# MCU.net
KiCad netlist of a schematic drawn in Altium Designer
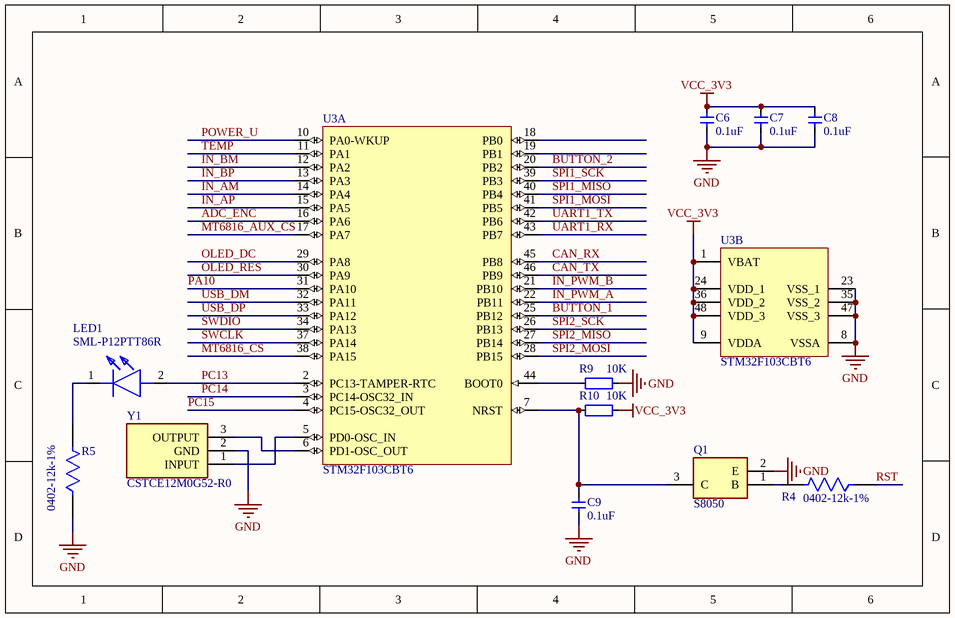
[diagram p0: MCU.SchDoc]

(export (version "E")
  (design (tool "Eeschema 10.0.6"))
  (components
    (comp (ref "C6")
      (value "0.1uF")
      (footprint "CAP_0402")
      (description "Capacitor")
      (libsource (lib "MyPcbLib") (part "电容-0402"))
    )
    (comp (ref "C7")
      (value "0.1uF")
      (footprint "CAP_0402")
      (description "Capacitor")
      (libsource (lib "MyPcbLib") (part "电容-0402"))
    )
    (comp (ref "C8")
      (value "0.1uF")
      (footprint "CAP_0402")
      (description "Capacitor")
      (libsource (lib "MyPcbLib") (part "电容-0402"))
    )
    (comp (ref "C9")
      (value "0.1uF")
      (footprint "CAP_0402")
      (description "Capacitor")
      (libsource (lib "MyPcbLib") (part "电容-0402"))
    )
    (comp (ref "LED1")
      (value "SML-P12PTT86R")
      (footprint "SamacSys:LEDC1006X25N")
      (description "LED")
      (fields (field (name "MOUSER PART NUMBER") "755-SML-P12PTT86R"))
      (libsource (lib "*") (part "SML-P12PTT86R"))
    )
    (comp (ref "Q1")
      (value "S8050")
      (footprint "SamacSys:SOT95P240X115-3N")
      (description "Transistor")
      (libsource (lib "SamacSys") (part "S8050"))
    )
    (comp (ref "R4")
      (value "0402-12k-1%")
      (footprint "FP-CRCW0402-e3-IPC_C")
      (description "RES Thick Film, 0Ω, 0.063W, 0402")
      (fields (field (name "TOLERANCE") "5%"))
      (libsource (lib "Altium Content Vault") (part "1029c3af85768c4190bb7ad29bc67b5"))
    )
    (comp (ref "R5")
      (value "0402-12k-1%")
      (footprint "FP-CRCW0402-e3-IPC_C")
      (description "RES Thick Film, 0Ω, 0.063W, 0402")
      (fields (field (name "TOLERANCE") "5%"))
      (libsource (lib "Altium Content Vault") (part "1029c3af85768c4190bb7ad29bc67b5"))
    )
    (comp (ref "R9")
      (value "10K")
      (footprint "RES_0402")
      (description "Resistor")
      (libsource (lib "MyPcbLib") (part "电阻-0402"))
    )
    (comp (ref "R10")
      (value "10K")
      (footprint "RES_0402")
      (description "Resistor")
      (libsource (lib "MyPcbLib") (part "电阻-0402"))
    )
    (comp (ref "U3")
      (value "STM32F103CBT6")
      (footprint "LQFP-48")
      (libsource (lib "STMicroelectronics STM32 F1") (part "STM32F103CBT6"))
    )
    (comp (ref "Y1")
      (value "CSTCE12M0G52-R0")
      (footprint "SamacSys:CSTCE12M0G52R0")
      (description "Crystal or Oscillator")
      (fields (field (name "MOUSER PART NUMBER") "81-CSTCE12M0G52-R0"))
      (libsource (lib "*") (part "CSTCE12M0G52-R0"))
    )
  )
  (nets
    (net (code "1") (name "/ADC_ENC") (class "Default")
      (node (ref "U3") (pin "16") (pinfunction "PA6_16") (pintype "bidirectional"))
    )
    (net (code "2") (name "/BUTTON_1") (class "Default")
      (node (ref "U3") (pin "25") (pinfunction "PB12_25") (pintype "bidirectional"))
    )
    (net (code "3") (name "/BUTTON_2") (class "Default")
      (node (ref "U3") (pin "20") (pinfunction "PB2_20") (pintype "bidirectional"))
    )
    (net (code "4") (name "/CAN_RX") (class "Default")
      (node (ref "U3") (pin "45") (pinfunction "PB8_45") (pintype "bidirectional"))
    )
    (net (code "5") (name "/CAN_TX") (class "Default")
      (node (ref "U3") (pin "46") (pinfunction "PB9_46") (pintype "bidirectional"))
    )
    (net (code "6") (name "/IN_AM") (class "Default")
      (node (ref "U3") (pin "14") (pinfunction "PA4_14") (pintype "bidirectional"))
    )
    (net (code "7") (name "/IN_AP") (class "Default")
      (node (ref "U3") (pin "15") (pinfunction "PA5_15") (pintype "bidirectional"))
    )
    (net (code "8") (name "/IN_BM") (class "Default")
      (node (ref "U3") (pin "12") (pinfunction "PA2_12") (pintype "bidirectional"))
    )
    (net (code "9") (name "/IN_BP") (class "Default")
      (node (ref "U3") (pin "13") (pinfunction "PA3_13") (pintype "bidirectional"))
    )
    (net (code "10") (name "/IN_PWM_A") (class "Default")
      (node (ref "U3") (pin "22") (pinfunction "PB11_22") (pintype "bidirectional"))
    )
    (net (code "11") (name "/IN_PWM_B") (class "Default")
      (node (ref "U3") (pin "21") (pinfunction "PB10_21") (pintype "bidirectional"))
    )
    (net (code "12") (name "/MT6816_AUX_CS") (class "Default")
      (node (ref "U3") (pin "17") (pinfunction "PA7_17") (pintype "bidirectional"))
    )
    (net (code "13") (name "/MT6816_CS") (class "Default")
      (node (ref "U3") (pin "38") (pinfunction "PA15_38") (pintype "bidirectional"))
    )
    (net (code "14") (name "/OLED_DC") (class "Default")
      (node (ref "U3") (pin "29") (pinfunction "PA8_29") (pintype "bidirectional"))
    )
    (net (code "15") (name "/OLED_RES") (class "Default")
      (node (ref "U3") (pin "30") (pinfunction "PA9_30") (pintype "bidirectional"))
    )
    (net (code "16") (name "/PA10") (class "Default")
      (node (ref "U3") (pin "31") (pinfunction "PA10_31") (pintype "bidirectional"))
    )
    (net (code "17") (name "/PC13") (class "Default")
      (node (ref "LED1") (pin "2") (pinfunction "A_2") (pintype "passive"))
      (node (ref "U3") (pin "2") (pinfunction "PC13-TAMPER-RTC_2") (pintype "bidirectional"))
    )
    (net (code "18") (name "/PC14") (class "Default")
      (node (ref "U3") (pin "3") (pinfunction "PC14-OSC32_IN_3") (pintype "bidirectional"))
    )
    (net (code "19") (name "/PC15") (class "Default")
      (node (ref "U3") (pin "4") (pinfunction "PC15-OSC32_OUT_4") (pintype "bidirectional"))
    )
    (net (code "20") (name "/POWER_U") (class "Default")
      (node (ref "U3") (pin "10") (pinfunction "PA0-WKUP_10") (pintype "bidirectional"))
    )
    (net (code "21") (name "/RST") (class "Default")
      (node (ref "R4") (pin "1") (pinfunction "1_1") (pintype "passive"))
    )
    (net (code "22") (name "/SPI1_MISO") (class "Default")
      (node (ref "U3") (pin "40") (pinfunction "PB4_40") (pintype "bidirectional"))
    )
    (net (code "23") (name "/SPI1_MOSI") (class "Default")
      (node (ref "U3") (pin "41") (pinfunction "PB5_41") (pintype "bidirectional"))
    )
    (net (code "24") (name "/SPI1_SCK") (class "Default")
      (node (ref "U3") (pin "39") (pinfunction "PB3_39") (pintype "bidirectional"))
    )
    (net (code "25") (name "/SPI2_MISO") (class "Default")
      (node (ref "U3") (pin "27") (pinfunction "PB14_27") (pintype "bidirectional"))
    )
    (net (code "26") (name "/SPI2_MOSI") (class "Default")
      (node (ref "U3") (pin "28") (pinfunction "PB15_28") (pintype "bidirectional"))
    )
    (net (code "27") (name "/SPI2_SCK") (class "Default")
      (node (ref "U3") (pin "26") (pinfunction "PB13_26") (pintype "bidirectional"))
    )
    (net (code "28") (name "/SWCLK") (class "Default")
      (node (ref "U3") (pin "37") (pinfunction "PA14_37") (pintype "bidirectional"))
    )
    (net (code "29") (name "/SWDIO") (class "Default")
      (node (ref "U3") (pin "34") (pinfunction "PA13_34") (pintype "bidirectional"))
    )
    (net (code "30") (name "/TEMP") (class "Default")
      (node (ref "U3") (pin "11") (pinfunction "PA1_11") (pintype "bidirectional"))
    )
    (net (code "31") (name "/UART1_RX") (class "Default")
      (node (ref "U3") (pin "43") (pinfunction "PB7_43") (pintype "bidirectional"))
    )
    (net (code "32") (name "/UART1_TX") (class "Default")
      (node (ref "U3") (pin "42") (pinfunction "PB6_42") (pintype "bidirectional"))
    )
    (net (code "33") (name "/USB_DM") (class "Default")
      (node (ref "U3") (pin "32") (pinfunction "PA11_32") (pintype "bidirectional"))
    )
    (net (code "34") (name "/USB_DP") (class "Default")
      (node (ref "U3") (pin "33") (pinfunction "PA12_33") (pintype "bidirectional"))
    )
    (net (code "35") (name "GND") (class "Default")
      (node (ref "C6") (pin "1") (pinfunction "1_1") (pintype "passive"))
      (node (ref "C7") (pin "1") (pinfunction "1_1") (pintype "passive"))
      (node (ref "C8") (pin "1") (pinfunction "1_1") (pintype "passive"))
      (node (ref "C9") (pin "1") (pinfunction "1_1") (pintype "passive"))
      (node (ref "Q1") (pin "2") (pinfunction "E_2") (pintype "passive"))
      (node (ref "R5") (pin "1") (pinfunction "1_1") (pintype "passive"))
      (node (ref "R9") (pin "2") (pinfunction "2_2") (pintype "passive"))
      (node (ref "U3") (pin "23") (pinfunction "VSS_1_23") (pintype "power_in"))
      (node (ref "U3") (pin "35") (pinfunction "VSS_2_35") (pintype "power_in"))
      (node (ref "U3") (pin "47") (pinfunction "VSS_3_47") (pintype "power_in"))
      (node (ref "U3") (pin "8") (pinfunction "VSSA_8") (pintype "power_in"))
      (node (ref "Y1") (pin "2") (pinfunction "GND_2") (pintype "passive"))
    )
    (net (code "36") (name "Net-(LED1-K)") (class "Default")
      (node (ref "LED1") (pin "1") (pinfunction "K_1") (pintype "passive"))
      (node (ref "R5") (pin "2") (pinfunction "2_2") (pintype "passive"))
    )
    (net (code "37") (name "Net-(Q1-B)") (class "Default")
      (node (ref "Q1") (pin "1") (pinfunction "B_1") (pintype "passive"))
      (node (ref "R4") (pin "2") (pinfunction "2_2") (pintype "passive"))
    )
    (net (code "38") (name "Net-(Q1-C)") (class "Default")
      (node (ref "C9") (pin "2") (pinfunction "2_2") (pintype "passive"))
      (node (ref "Q1") (pin "3") (pinfunction "C_3") (pintype "passive"))
      (node (ref "R10") (pin "1") (pinfunction "1_1") (pintype "passive"))
      (node (ref "U3") (pin "7") (pinfunction "NRST_7") (pintype "bidirectional"))
    )
    (net (code "39") (name "Net-(U3A-BOOT0)") (class "Default")
      (node (ref "R9") (pin "1") (pinfunction "1_1") (pintype "passive"))
      (node (ref "U3") (pin "44") (pinfunction "BOOT0_44") (pintype "input"))
    )
    (net (code "40") (name "Net-(U3A-PD0-OSC_IN)") (class "Default")
      (node (ref "U3") (pin "5") (pinfunction "PD0-OSC_IN_5") (pintype "bidirectional"))
      (node (ref "Y1") (pin "1") (pinfunction "INPUT_1") (pintype "passive"))
    )
    (net (code "41") (name "Net-(U3A-PD1-OSC_OUT)") (class "Default")
      (node (ref "U3") (pin "6") (pinfunction "PD1-OSC_OUT_6") (pintype "bidirectional"))
      (node (ref "Y1") (pin "3") (pinfunction "OUTPUT_3") (pintype "passive"))
    )
    (net (code "42") (name "VCC_3V3") (class "Default")
      (node (ref "C6") (pin "2") (pinfunction "2_2") (pintype "passive"))
      (node (ref "C7") (pin "2") (pinfunction "2_2") (pintype "passive"))
      (node (ref "C8") (pin "2") (pinfunction "2_2") (pintype "passive"))
      (node (ref "R10") (pin "2") (pinfunction "2_2") (pintype "passive"))
      (node (ref "U3") (pin "1") (pinfunction "VBAT_1") (pintype "power_in"))
      (node (ref "U3") (pin "24") (pinfunction "VDD_1_24") (pintype "power_in"))
      (node (ref "U3") (pin "36") (pinfunction "VDD_2_36") (pintype "power_in"))
      (node (ref "U3") (pin "48") (pinfunction "VDD_3_48") (pintype "power_in"))
      (node (ref "U3") (pin "9") (pinfunction "VDDA_9") (pintype "power_in"))
    )
    (net (code "43") (name "unconnected-(U3A-PB0-Pad18)") (class "Default")
      (node (ref "U3") (pin "18") (pinfunction "PB0_18") (pintype "bidirectional"))
    )
    (net (code "44") (name "unconnected-(U3A-PB1-Pad19)") (class "Default")
      (node (ref "U3") (pin "19") (pinfunction "PB1_19") (pintype "bidirectional"))
    )
  )
)
